# DBMSch.net
KiCad netlist of a schematic drawn in Altium Designer
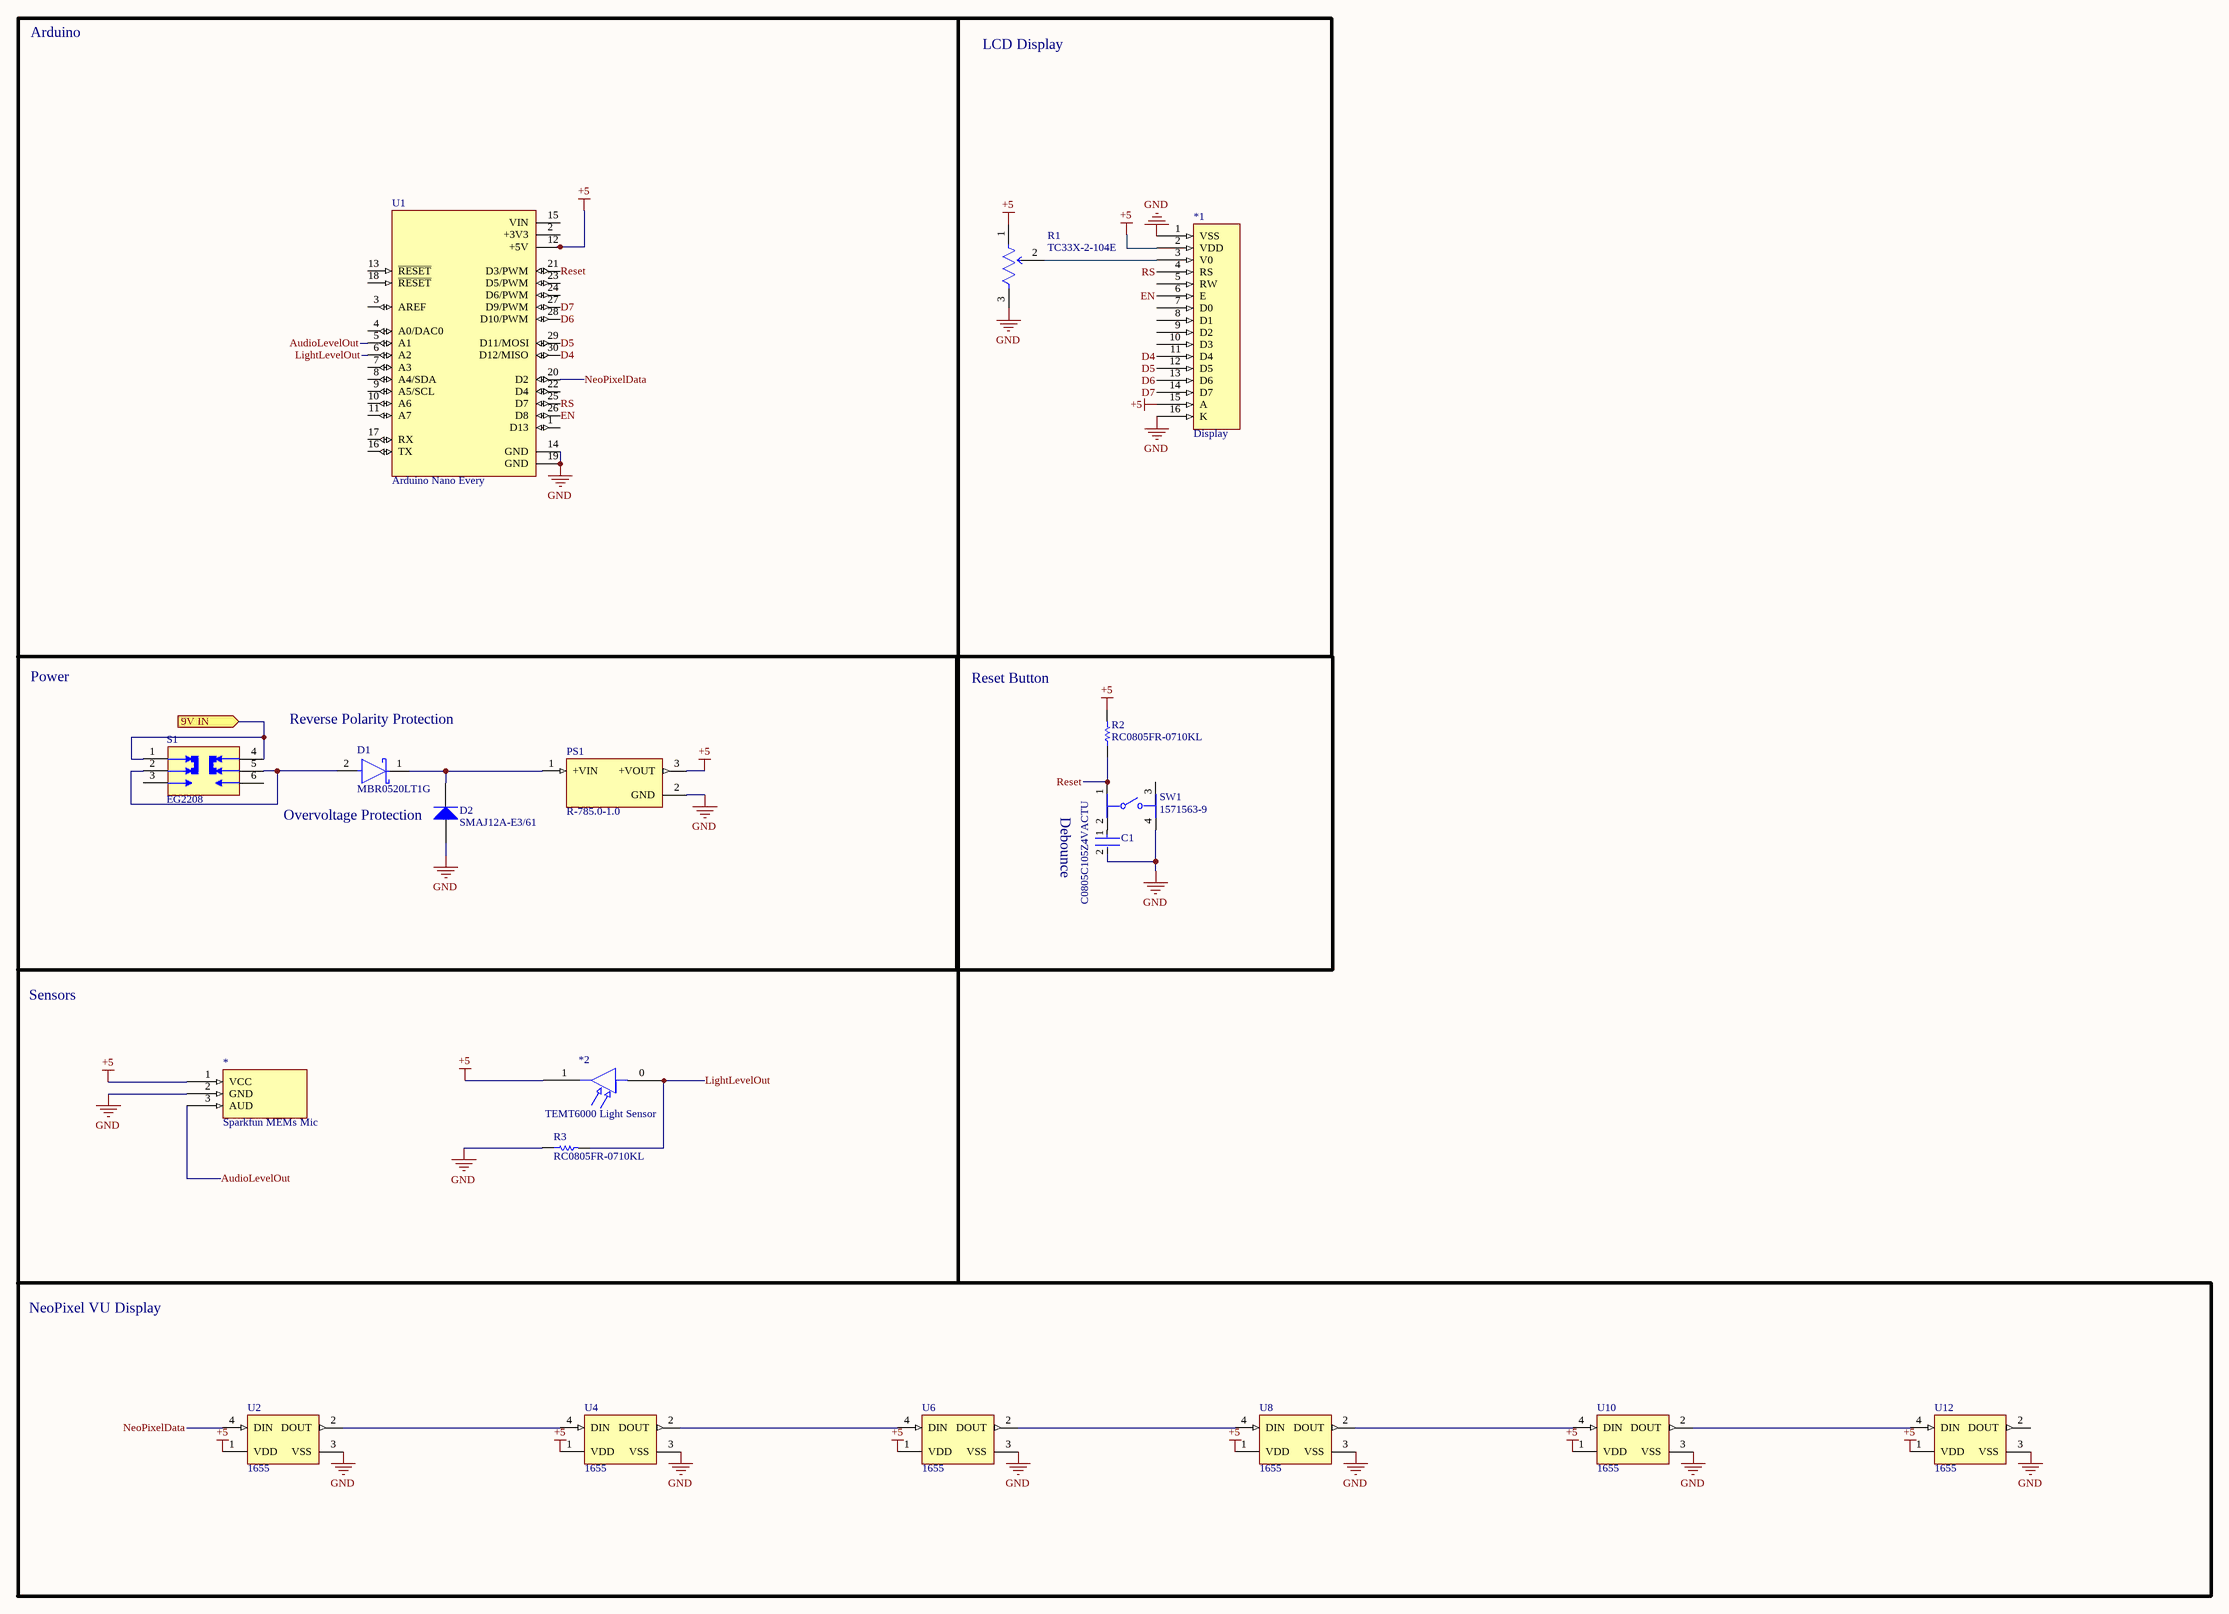
[diagram p0: DBMSch.SchDoc]

(export (version "E")
  (design (tool "Eeschema 10.0.6"))
  (components
    (comp (ref "*")
      (value "Sparkfun MEMs Mic")
      (footprint "MEMs Mic Board")
      (libsource (lib "DBM") (part "Sparkfun MEMs Mic"))
    )
    (comp (ref "*1")
      (value "Display")
      (footprint "Screen")
      (libsource (lib "RiceCookerLib") (part "Display"))
    )
    (comp (ref "*2")
      (value "TEMT6000 Light Sensor")
      (footprint "Light Sensor")
      (libsource (lib "DBM") (part "Light Sensor"))
    )
    (comp (ref "C1")
      (value "C0805C105Z4VACTU")
      (footprint "FP-C0805C105Z4VACTU-MFG")
      (description "CAP CER 1UF 16V Y5V 0805")
      (fields (field (name "VOLTAGE") "16V") (field (name "TOLERANCE") "80%"))
      (libsource (lib "Altium Content Vault") (part "02cd4be3c70576c341d710602a673aa"))
    )
    (comp (ref "D1")
      (value "MBR0520LT1G")
      (footprint "FP-425-04-IPC_C")
      (description "DIODE SCHOTTKY 20V 500MA SOD123")
      (libsource (lib "Altium Content Vault") (part "1d6ec82d83fb6aee721767c19dac4b9"))
    )
    (comp (ref "D2")
      (value "SMAJ12A-E3/61")
      (footprint "VISH-DO-214AC-2_N")
      (fields (field (name "MANUFACTURER") "Vishay Semiconductor"))
      (libsource (lib "Altium Content Vault") (part "VISH-K1A2-2"))
    )
    (comp (ref "PS1")
      (value "R-785.0-1.0")
      (footprint "CONV_R-785.0-1.0")
      (description "1.0 Amp SIP3 Single Output")
      (fields (field (name "MF") "{'manufacturer': u'Recom Power'}"))
      (libsource (lib "R-785.0-1.0") (part "R-785.0-1.0"))
    )
    (comp (ref "R1")
      (value "TC33X-2-104E")
      (footprint "FP-TC33X-2-MFG")
      (description "TRIMMER 100K OHM 0.1W J LEAD TOP")
      (fields (field (name "TOLERANCE") "25%"))
      (libsource (lib "Altium Content Vault") (part "13357d81287629c2fd191d242cfa50c"))
    )
    (comp (ref "R2")
      (value "RC0805FR-0710KL")
      (footprint "RESC2013X60X35NL10T20")
      (description "Chip Resistor, 10 KOhm, +/- 1%, 0.125 W, -55 to 155 degC, 0805 (2012 Metric), RoHS, Tape and Reel")
      (fields (field (name "MANUFACTURER") "Yageo"))
      (libsource (lib "Altium Content Vault") (part "RES-2"))
    )
    (comp (ref "R3")
      (value "RC0805FR-0710KL")
      (footprint "RESC2013X60X35NL10T20")
      (description "Chip Resistor, 10 KOhm, +/- 1%, 0.125 W, -55 to 155 degC, 0805 (2012 Metric), RoHS, Tape and Reel")
      (fields (field (name "MANUFACTURER") "Yageo"))
      (libsource (lib "Altium Content Vault") (part "RES-2"))
    )
    (comp (ref "S1")
      (value "EG2208")
      (footprint "EG2208:SW_EG2208")
      (fields (field (name "MF") "{'manufacturer': u'E-Switch'}"))
      (libsource (lib "EG2208") (part "EG2208"))
    )
    (comp (ref "SW1")
      (value "1571563-9")
      (footprint "FP-1571563-9-MFG")
      (description "SWITCH TACTILE SPST-NO 0.05A 24V")
      (fields
        (field (name "MANUFACTURER") "TE Connectivity")
        (field (name "OCTOPART") "https://octopart.com/1571563-9-te+connectivity-41253969")
      )
      (libsource (lib "Altium Content Vault") (part "b8895f3f4cefb76e1819d2863dba89b"))
    )
    (comp (ref "U1")
      (value "Arduino Nano Every")
      (footprint "MODULE_ABX00028")
      (description "ATmega4809 Arduino Nano Every AVR AVR MCU 8-Bit Embedded Evaluation Board")
      (fields (field (name "MP") "ABX00028") (field (name "MF") "{'manufacturer': u'Arduino'}"))
      (libsource (lib "Arduino Nano Every") (part "ABX00028"))
    )
    (comp (ref "U2")
      (value "1655")
      (footprint "ADA-RGB-1655_V")
      (fields (field (name "MANUFACTURER") "Adafruit-Industries-LLC"))
      (libsource (lib "Altium Content Vault") (part "ADA-RGB-1655-4"))
    )
    (comp (ref "U4")
      (value "1655")
      (footprint "ADA-RGB-1655_V")
      (fields (field (name "MANUFACTURER") "Adafruit-Industries-LLC"))
      (libsource (lib "Altium Content Vault") (part "ADA-RGB-1655-4"))
    )
    (comp (ref "U6")
      (value "1655")
      (footprint "ADA-RGB-1655_V")
      (fields (field (name "MANUFACTURER") "Adafruit-Industries-LLC"))
      (libsource (lib "Altium Content Vault") (part "ADA-RGB-1655-4"))
    )
    (comp (ref "U8")
      (value "1655")
      (footprint "ADA-RGB-1655_V")
      (fields (field (name "MANUFACTURER") "Adafruit-Industries-LLC"))
      (libsource (lib "Altium Content Vault") (part "ADA-RGB-1655-4"))
    )
    (comp (ref "U10")
      (value "1655")
      (footprint "ADA-RGB-1655_V")
      (fields (field (name "MANUFACTURER") "Adafruit-Industries-LLC"))
      (libsource (lib "Altium Content Vault") (part "ADA-RGB-1655-4"))
    )
    (comp (ref "U12")
      (value "1655")
      (footprint "ADA-RGB-1655_V")
      (fields (field (name "MANUFACTURER") "Adafruit-Industries-LLC"))
      (libsource (lib "Altium Content Vault") (part "ADA-RGB-1655-4"))
    )
  )
  (nets
    (net (code "1") (name "+5") (class "Default")
      (node (ref "*") (pin "1") (pinfunction "VCC_1") (pintype "input"))
      (node (ref "*1") (pin "15") (pinfunction "A_15") (pintype "input"))
      (node (ref "*1") (pin "2") (pinfunction "VDD_2") (pintype "input"))
      (node (ref "*2") (pin "1") (pinfunction "1_1") (pintype "passive"))
      (node (ref "PS1") (pin "3") (pinfunction "+VOUT_3") (pintype "output"))
      (node (ref "R1") (pin "1") (pinfunction "CCW_1") (pintype "passive"))
      (node (ref "R2") (pin "2") (pinfunction "2_2") (pintype "passive"))
      (node (ref "U1") (pin "12") (pinfunction "+5V_12") (pintype "power_in"))
      (node (ref "U10") (pin "1") (pinfunction "VDD_1") (pintype "power_in"))
      (node (ref "U12") (pin "1") (pinfunction "VDD_1") (pintype "power_in"))
      (node (ref "U2") (pin "1") (pinfunction "VDD_1") (pintype "power_in"))
      (node (ref "U4") (pin "1") (pinfunction "VDD_1") (pintype "power_in"))
      (node (ref "U6") (pin "1") (pinfunction "VDD_1") (pintype "power_in"))
      (node (ref "U8") (pin "1") (pinfunction "VDD_1") (pintype "power_in"))
    )
    (net (code "2") (name "/9V IN") (class "Default")
      (node (ref "S1") (pin "1") (pinfunction "1_1") (pintype "passive"))
      (node (ref "S1") (pin "4") (pinfunction "4_4") (pintype "passive"))
    )
    (net (code "3") (name "/AudioLevelOut") (class "Default")
      (node (ref "*") (pin "3") (pinfunction "AUD_3") (pintype "input"))
      (node (ref "U1") (pin "5") (pinfunction "A1_5") (pintype "bidirectional"))
    )
    (net (code "4") (name "/D4") (class "Default")
      (node (ref "*1") (pin "11") (pinfunction "D4_11") (pintype "input"))
      (node (ref "U1") (pin "30") (pinfunction "D12/MISO_30") (pintype "bidirectional"))
    )
    (net (code "5") (name "/D5") (class "Default")
      (node (ref "*1") (pin "12") (pinfunction "D5_12") (pintype "input"))
      (node (ref "U1") (pin "29") (pinfunction "D11/MOSI_29") (pintype "bidirectional"))
    )
    (net (code "6") (name "/D6") (class "Default")
      (node (ref "*1") (pin "13") (pinfunction "D6_13") (pintype "input"))
      (node (ref "U1") (pin "28") (pinfunction "D10/PWM_28") (pintype "bidirectional"))
    )
    (net (code "7") (name "/D7") (class "Default")
      (node (ref "*1") (pin "14") (pinfunction "D7_14") (pintype "input"))
      (node (ref "U1") (pin "27") (pinfunction "D9/PWM_27") (pintype "bidirectional"))
    )
    (net (code "8") (name "/EN") (class "Default")
      (node (ref "*1") (pin "6") (pinfunction "E_6") (pintype "input"))
      (node (ref "U1") (pin "26") (pinfunction "D8_26") (pintype "bidirectional"))
    )
    (net (code "9") (name "/LightLevelOut") (class "Default")
      (node (ref "*2") (pin "0") (pinfunction "0_0") (pintype "passive"))
      (node (ref "R3") (pin "2") (pinfunction "2_2") (pintype "passive"))
      (node (ref "U1") (pin "6") (pinfunction "A2_6") (pintype "bidirectional"))
    )
    (net (code "10") (name "/NeoPixelData") (class "Default")
      (node (ref "U1") (pin "20") (pinfunction "D2_20") (pintype "bidirectional"))
      (node (ref "U2") (pin "4") (pinfunction "DIN_4") (pintype "input"))
    )
    (net (code "11") (name "/RS") (class "Default")
      (node (ref "*1") (pin "4") (pinfunction "RS_4") (pintype "input"))
      (node (ref "U1") (pin "25") (pinfunction "D7_25") (pintype "bidirectional"))
    )
    (net (code "12") (name "/Reset") (class "Default")
      (node (ref "R2") (pin "1") (pinfunction "1_1") (pintype "passive"))
      (node (ref "SW1") (pin "1") (pinfunction "1_1") (pintype "passive"))
      (node (ref "U1") (pin "21") (pinfunction "D3/PWM_21") (pintype "bidirectional"))
    )
    (net (code "13") (name "GND") (class "Default")
      (node (ref "*") (pin "2") (pinfunction "GND_2") (pintype "input"))
      (node (ref "*1") (pin "1") (pinfunction "VSS_1") (pintype "input"))
      (node (ref "*1") (pin "16") (pinfunction "K_16") (pintype "input"))
      (node (ref "C1") (pin "2") (pinfunction "2_2") (pintype "passive"))
      (node (ref "D2") (pin "2") (pinfunction "A_2") (pintype "passive"))
      (node (ref "PS1") (pin "2") (pinfunction "GND_2") (pintype "power_in"))
      (node (ref "R1") (pin "3") (pinfunction "CW_3") (pintype "passive"))
      (node (ref "R3") (pin "1") (pinfunction "1_1") (pintype "passive"))
      (node (ref "SW1") (pin "4") (pinfunction "4_4") (pintype "passive"))
      (node (ref "U1") (pin "14") (pinfunction "GND_14") (pintype "power_in"))
      (node (ref "U1") (pin "19") (pinfunction "GND_19") (pintype "power_in"))
      (node (ref "U10") (pin "3") (pinfunction "VSS_3") (pintype "power_in"))
      (node (ref "U12") (pin "3") (pinfunction "VSS_3") (pintype "power_in"))
      (node (ref "U2") (pin "3") (pinfunction "VSS_3") (pintype "power_in"))
      (node (ref "U4") (pin "3") (pinfunction "VSS_3") (pintype "power_in"))
      (node (ref "U6") (pin "3") (pinfunction "VSS_3") (pintype "power_in"))
      (node (ref "U8") (pin "3") (pinfunction "VSS_3") (pintype "power_in"))
    )
    (net (code "14") (name "Net-(*1-V0)") (class "Default")
      (node (ref "*1") (pin "3") (pinfunction "V0_3") (pintype "input"))
      (node (ref "R1") (pin "2") (pinfunction "WIPER_2") (pintype "passive"))
    )
    (net (code "15") (name "Net-(C1-Pad1)") (class "Default")
      (node (ref "C1") (pin "1") (pinfunction "1_1") (pintype "passive"))
      (node (ref "SW1") (pin "2") (pinfunction "2_2") (pintype "passive"))
    )
    (net (code "16") (name "Net-(D1-A)") (class "Default")
      (node (ref "D1") (pin "2") (pinfunction "A_2") (pintype "passive"))
      (node (ref "S1") (pin "2") (pinfunction "2_2") (pintype "passive"))
      (node (ref "S1") (pin "5") (pinfunction "5_5") (pintype "passive"))
    )
    (net (code "17") (name "Net-(D1-C)") (class "Default")
      (node (ref "D1") (pin "1") (pinfunction "C_1") (pintype "passive"))
      (node (ref "D2") (pin "1") (pinfunction "K_1") (pintype "passive"))
      (node (ref "PS1") (pin "1") (pinfunction "+VIN_1") (pintype "input"))
    )
    (net (code "18") (name "Net-(U2-DOUT)") (class "Default")
      (node (ref "U2") (pin "2") (pinfunction "DOUT_2") (pintype "output"))
      (node (ref "U4") (pin "4") (pinfunction "DIN_4") (pintype "input"))
    )
    (net (code "19") (name "Net-(U4-DOUT)") (class "Default")
      (node (ref "U4") (pin "2") (pinfunction "DOUT_2") (pintype "output"))
      (node (ref "U6") (pin "4") (pinfunction "DIN_4") (pintype "input"))
    )
    (net (code "20") (name "Net-(U6-DOUT)") (class "Default")
      (node (ref "U6") (pin "2") (pinfunction "DOUT_2") (pintype "output"))
      (node (ref "U8") (pin "4") (pinfunction "DIN_4") (pintype "input"))
    )
    (net (code "21") (name "Net-(U10-DIN)") (class "Default")
      (node (ref "U10") (pin "4") (pinfunction "DIN_4") (pintype "input"))
      (node (ref "U8") (pin "2") (pinfunction "DOUT_2") (pintype "output"))
    )
    (net (code "22") (name "Net-(U10-DOUT)") (class "Default")
      (node (ref "U10") (pin "2") (pinfunction "DOUT_2") (pintype "output"))
      (node (ref "U12") (pin "4") (pinfunction "DIN_4") (pintype "input"))
    )
    (net (code "23") (name "unconnected-(*1-D0-Pad7)") (class "Default")
      (node (ref "*1") (pin "7") (pinfunction "D0_7") (pintype "input"))
    )
    (net (code "24") (name "unconnected-(*1-D1-Pad8)") (class "Default")
      (node (ref "*1") (pin "8") (pinfunction "D1_8") (pintype "input"))
    )
    (net (code "25") (name "unconnected-(*1-D2-Pad9)") (class "Default")
      (node (ref "*1") (pin "9") (pinfunction "D2_9") (pintype "input"))
    )
    (net (code "26") (name "unconnected-(*1-D3-Pad10)") (class "Default")
      (node (ref "*1") (pin "10") (pinfunction "D3_10") (pintype "input"))
    )
    (net (code "27") (name "unconnected-(*1-RW-Pad5)") (class "Default")
      (node (ref "*1") (pin "5") (pinfunction "RW_5") (pintype "input"))
    )
    (net (code "28") (name "unconnected-(S1-Pad3)") (class "Default")
      (node (ref "S1") (pin "3") (pinfunction "3_3") (pintype "passive"))
    )
    (net (code "29") (name "unconnected-(S1-Pad6)") (class "Default")
      (node (ref "S1") (pin "6") (pinfunction "6_6") (pintype "passive"))
    )
    (net (code "30") (name "unconnected-(SW1-Pad3)") (class "Default")
      (node (ref "SW1") (pin "3") (pinfunction "3_3") (pintype "passive"))
    )
    (net (code "31") (name "unconnected-(U1-+3V3-Pad2)") (class "Default")
      (node (ref "U1") (pin "2") (pinfunction "+3V3_2") (pintype "power_in"))
    )
    (net (code "32") (name "unconnected-(U1-A0{slash}DAC0-Pad4)") (class "Default")
      (node (ref "U1") (pin "4") (pinfunction "A0/DAC0_4") (pintype "bidirectional"))
    )
    (net (code "33") (name "unconnected-(U1-A3-Pad7)") (class "Default")
      (node (ref "U1") (pin "7") (pinfunction "A3_7") (pintype "bidirectional"))
    )
    (net (code "34") (name "unconnected-(U1-A4{slash}SDA-Pad8)") (class "Default")
      (node (ref "U1") (pin "8") (pinfunction "A4/SDA_8") (pintype "bidirectional"))
    )
    (net (code "35") (name "unconnected-(U1-A5{slash}SCL-Pad9)") (class "Default")
      (node (ref "U1") (pin "9") (pinfunction "A5/SCL_9") (pintype "bidirectional"))
    )
    (net (code "36") (name "unconnected-(U1-A6-Pad10)") (class "Default")
      (node (ref "U1") (pin "10") (pinfunction "A6_10") (pintype "bidirectional"))
    )
    (net (code "37") (name "unconnected-(U1-A7-Pad11)") (class "Default")
      (node (ref "U1") (pin "11") (pinfunction "A7_11") (pintype "bidirectional"))
    )
    (net (code "38") (name "unconnected-(U1-AREF-Pad3)") (class "Default")
      (node (ref "U1") (pin "3") (pinfunction "AREF_3") (pintype "bidirectional"))
    )
    (net (code "39") (name "unconnected-(U1-D4-Pad22)") (class "Default")
      (node (ref "U1") (pin "22") (pinfunction "D4_22") (pintype "bidirectional"))
    )
    (net (code "40") (name "unconnected-(U1-D5{slash}PWM-Pad23)") (class "Default")
      (node (ref "U1") (pin "23") (pinfunction "D5/PWM_23") (pintype "bidirectional"))
    )
    (net (code "41") (name "unconnected-(U1-D6{slash}PWM-Pad24)") (class "Default")
      (node (ref "U1") (pin "24") (pinfunction "D6/PWM_24") (pintype "bidirectional"))
    )
    (net (code "42") (name "unconnected-(U1-D13-Pad1)") (class "Default")
      (node (ref "U1") (pin "1") (pinfunction "D13_1") (pintype "bidirectional"))
    )
    (net (code "43") (name "unconnected-(U1-RX-Pad17)") (class "Default")
      (node (ref "U1") (pin "17") (pinfunction "RX_17") (pintype "bidirectional"))
    )
    (net (code "44") (name "unconnected-(U1-TX-Pad16)") (class "Default")
      (node (ref "U1") (pin "16") (pinfunction "TX_16") (pintype "bidirectional"))
    )
    (net (code "45") (name "unconnected-(U1-VIN-Pad15)") (class "Default")
      (node (ref "U1") (pin "15") (pinfunction "VIN_15") (pintype "power_in"))
    )
    (net (code "46") (name "unconnected-(U1-~{RESET}-Pad13)") (class "Default")
      (node (ref "U1") (pin "13") (pinfunction "~{RESET}_13") (pintype "input"))
    )
    (net (code "47") (name "unconnected-(U1-~{RESET}-Pad18)") (class "Default")
      (node (ref "U1") (pin "18") (pinfunction "~{RESET}_18") (pintype "input"))
    )
    (net (code "48") (name "unconnected-(U12-DOUT-Pad2)") (class "Default")
      (node (ref "U12") (pin "2") (pinfunction "DOUT_2") (pintype "output"))
    )
  )
)
